# 40106PWM.net
KiCad netlist of a schematic drawn in EAGLE
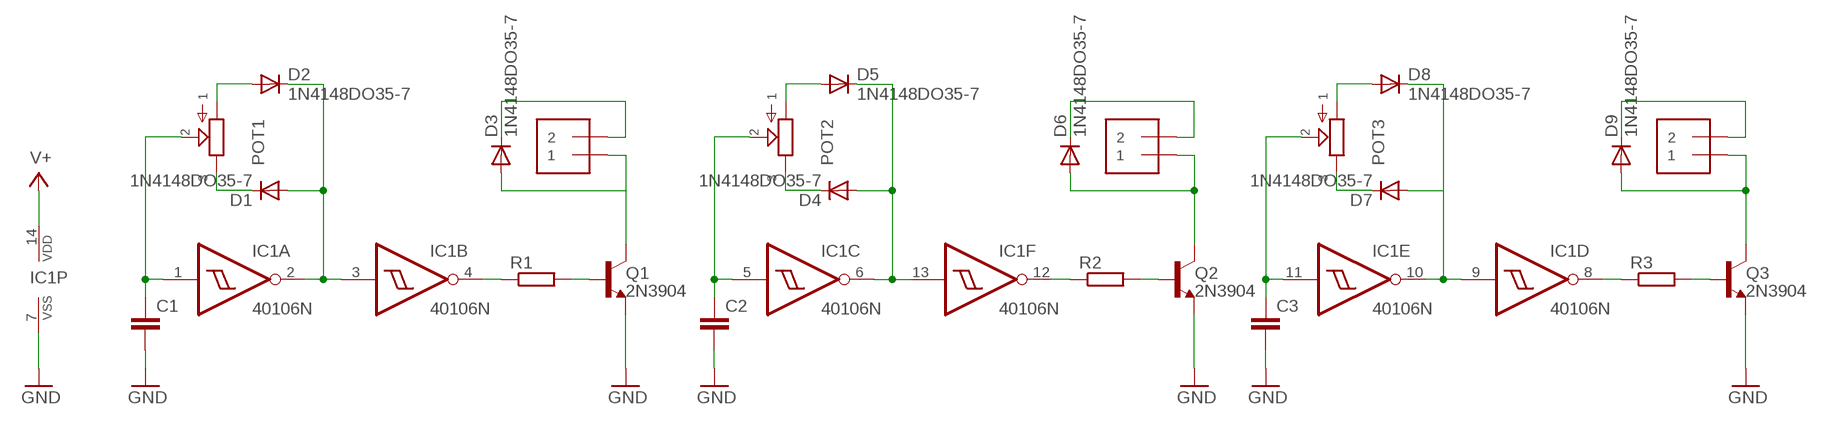
[diagram p0: schematic, sheet 1]

(export (version "E")
  (design (tool "Eeschema 10.0.6"))
  (components
    (comp (ref "C1")
      (value "C-EU050-025X075")
      (footprint "eagle-import:C050-025X075")
      (libsource (lib "eagle-import") (part "C-EU050-025X075"))
    )
    (comp (ref "C2")
      (value "C-EU050-025X075")
      (footprint "eagle-import:C050-025X075")
      (libsource (lib "eagle-import") (part "C-EU050-025X075"))
    )
    (comp (ref "C3")
      (value "C-EU050-025X075")
      (footprint "eagle-import:C050-025X075")
      (libsource (lib "eagle-import") (part "C-EU050-025X075"))
    )
    (comp (ref "D1")
      (value "1N4148DO35-7")
      (footprint "eagle-import:DO35-7")
      (libsource (lib "eagle-import") (part "1N4148DO35-7"))
    )
    (comp (ref "D2")
      (value "1N4148DO35-7")
      (footprint "eagle-import:DO35-7")
      (libsource (lib "eagle-import") (part "1N4148DO35-7"))
    )
    (comp (ref "D3")
      (value "1N4148DO35-7")
      (footprint "eagle-import:DO35-7")
      (libsource (lib "eagle-import") (part "1N4148DO35-7"))
    )
    (comp (ref "D4")
      (value "1N4148DO35-7")
      (footprint "eagle-import:DO35-7")
      (libsource (lib "eagle-import") (part "1N4148DO35-7"))
    )
    (comp (ref "D5")
      (value "1N4148DO35-7")
      (footprint "eagle-import:DO35-7")
      (libsource (lib "eagle-import") (part "1N4148DO35-7"))
    )
    (comp (ref "D6")
      (value "1N4148DO35-7")
      (footprint "eagle-import:DO35-7")
      (libsource (lib "eagle-import") (part "1N4148DO35-7"))
    )
    (comp (ref "D7")
      (value "1N4148DO35-7")
      (footprint "eagle-import:DO35-7")
      (libsource (lib "eagle-import") (part "1N4148DO35-7"))
    )
    (comp (ref "D8")
      (value "1N4148DO35-7")
      (footprint "eagle-import:DO35-7")
      (libsource (lib "eagle-import") (part "1N4148DO35-7"))
    )
    (comp (ref "D9")
      (value "1N4148DO35-7")
      (footprint "eagle-import:DO35-7")
      (libsource (lib "eagle-import") (part "1N4148DO35-7"))
    )
    (comp (ref "IC1")
      (value "40106N")
      (footprint "eagle-import:DIL14")
      (libsource (lib "eagle-import") (part "40106N"))
    )
    (comp (ref "J1")
      (value "1X2-3.5MM")
      (footprint "eagle-import:1X2-3.5MM")
      (libsource (lib "eagle-import") (part "1X2-3.5MM"))
    )
    (comp (ref "J2")
      (value "1X2-3.5MM")
      (footprint "eagle-import:1X2-3.5MM")
      (libsource (lib "eagle-import") (part "1X2-3.5MM"))
    )
    (comp (ref "J3")
      (value "1X2-3.5MM")
      (footprint "eagle-import:1X2-3.5MM")
      (libsource (lib "eagle-import") (part "1X2-3.5MM"))
    )
    (comp (ref "POT1")
      (value "POT-EU16MM")
      (footprint "eagle-import:16MM")
      (libsource (lib "eagle-import") (part "POT-EU16MM"))
    )
    (comp (ref "POT2")
      (value "POT-EU16MM")
      (footprint "eagle-import:16MM")
      (libsource (lib "eagle-import") (part "POT-EU16MM"))
    )
    (comp (ref "POT3")
      (value "POT-EU16MM")
      (footprint "eagle-import:16MM")
      (libsource (lib "eagle-import") (part "POT-EU16MM"))
    )
    (comp (ref "Q1")
      (value "2N3904")
      (footprint "eagle-import:TO92-")
      (libsource (lib "eagle-import") (part "2N3904"))
    )
    (comp (ref "Q2")
      (value "2N3904")
      (footprint "eagle-import:TO92-")
      (libsource (lib "eagle-import") (part "2N3904"))
    )
    (comp (ref "Q3")
      (value "2N3904")
      (footprint "eagle-import:TO92-")
      (libsource (lib "eagle-import") (part "2N3904"))
    )
    (comp (ref "R1")
      (value "R-EU_0207/10")
      (footprint "eagle-import:0207_10")
      (libsource (lib "eagle-import") (part "R-EU_0207/10"))
    )
    (comp (ref "R2")
      (value "R-EU_0207/10")
      (footprint "eagle-import:0207_10")
      (libsource (lib "eagle-import") (part "R-EU_0207/10"))
    )
    (comp (ref "R3")
      (value "R-EU_0207/10")
      (footprint "eagle-import:0207_10")
      (libsource (lib "eagle-import") (part "R-EU_0207/10"))
    )
  )
  (nets
    (net (code "1") (name "GND") (class "Default")
      (node (ref "C1") (pin "2") (pinfunction "2_2") (pintype "passive"))
      (node (ref "C2") (pin "2") (pinfunction "2_2") (pintype "passive"))
      (node (ref "C3") (pin "2") (pinfunction "2_2") (pintype "passive"))
      (node (ref "IC1") (pin "7") (pinfunction "VSS_7") (pintype "power_in"))
      (node (ref "Q1") (pin "3") (pinfunction "E_3") (pintype "passive"))
      (node (ref "Q2") (pin "3") (pinfunction "E_3") (pintype "passive"))
      (node (ref "Q3") (pin "3") (pinfunction "E_3") (pintype "passive"))
    )
    (net (code "2") (name "Net-(D1-PadC)") (class "Default")
      (node (ref "D1") (pin "C") (pinfunction "C_C") (pintype "passive"))
      (node (ref "POT1") (pin "3") (pinfunction "3_3") (pintype "passive"))
    )
    (net (code "3") (name "Net-(D2-PadA)") (class "Default")
      (node (ref "D2") (pin "A") (pinfunction "A_A") (pintype "passive"))
      (node (ref "POT1") (pin "1") (pinfunction "1_1") (pintype "passive"))
    )
    (net (code "4") (name "Net-(D3-PadC)") (class "Default")
      (node (ref "D3") (pin "C") (pinfunction "C_C") (pintype "passive"))
      (node (ref "J1") (pin "2") (pinfunction "2_2") (pintype "passive"))
    )
    (net (code "5") (name "Net-(D4-PadC)") (class "Default")
      (node (ref "D4") (pin "C") (pinfunction "C_C") (pintype "passive"))
      (node (ref "POT2") (pin "3") (pinfunction "3_3") (pintype "passive"))
    )
    (net (code "6") (name "Net-(D5-PadA)") (class "Default")
      (node (ref "D5") (pin "A") (pinfunction "A_A") (pintype "passive"))
      (node (ref "POT2") (pin "1") (pinfunction "1_1") (pintype "passive"))
    )
    (net (code "7") (name "Net-(D6-PadC)") (class "Default")
      (node (ref "D6") (pin "C") (pinfunction "C_C") (pintype "passive"))
      (node (ref "J2") (pin "2") (pinfunction "2_2") (pintype "passive"))
    )
    (net (code "8") (name "Net-(D7-PadC)") (class "Default")
      (node (ref "D7") (pin "C") (pinfunction "C_C") (pintype "passive"))
      (node (ref "POT3") (pin "3") (pinfunction "3_3") (pintype "passive"))
    )
    (net (code "9") (name "Net-(D8-PadA)") (class "Default")
      (node (ref "D8") (pin "A") (pinfunction "A_A") (pintype "passive"))
      (node (ref "POT3") (pin "1") (pinfunction "1_1") (pintype "passive"))
    )
    (net (code "10") (name "Net-(D9-PadC)") (class "Default")
      (node (ref "D9") (pin "C") (pinfunction "C_C") (pintype "passive"))
      (node (ref "J3") (pin "2") (pinfunction "2_2") (pintype "passive"))
    )
    (net (code "11") (name "Net-(IC1A-I)") (class "Default")
      (node (ref "C1") (pin "1") (pinfunction "1_1") (pintype "passive"))
      (node (ref "IC1") (pin "1") (pinfunction "I_1") (pintype "input"))
      (node (ref "POT1") (pin "2") (pinfunction "2_2") (pintype "passive"))
    )
    (net (code "12") (name "Net-(IC1A-O)") (class "Default")
      (node (ref "D1") (pin "A") (pinfunction "A_A") (pintype "passive"))
      (node (ref "D2") (pin "C") (pinfunction "C_C") (pintype "passive"))
      (node (ref "IC1") (pin "2") (pinfunction "O_2") (pintype "output"))
      (node (ref "IC1") (pin "3") (pinfunction "I_3") (pintype "input"))
    )
    (net (code "13") (name "Net-(IC1B-O)") (class "Default")
      (node (ref "IC1") (pin "4") (pinfunction "O_4") (pintype "output"))
      (node (ref "R1") (pin "1") (pinfunction "1_1") (pintype "passive"))
    )
    (net (code "14") (name "Net-(IC1C-I)") (class "Default")
      (node (ref "C2") (pin "1") (pinfunction "1_1") (pintype "passive"))
      (node (ref "IC1") (pin "5") (pinfunction "I_5") (pintype "input"))
      (node (ref "POT2") (pin "2") (pinfunction "2_2") (pintype "passive"))
    )
    (net (code "15") (name "Net-(IC1C-O)") (class "Default")
      (node (ref "D4") (pin "A") (pinfunction "A_A") (pintype "passive"))
      (node (ref "D5") (pin "C") (pinfunction "C_C") (pintype "passive"))
      (node (ref "IC1") (pin "13") (pinfunction "I_13") (pintype "input"))
      (node (ref "IC1") (pin "6") (pinfunction "O_6") (pintype "output"))
    )
    (net (code "16") (name "Net-(IC1D-I)") (class "Default")
      (node (ref "D7") (pin "A") (pinfunction "A_A") (pintype "passive"))
      (node (ref "D8") (pin "C") (pinfunction "C_C") (pintype "passive"))
      (node (ref "IC1") (pin "10") (pinfunction "O_10") (pintype "output"))
      (node (ref "IC1") (pin "9") (pinfunction "I_9") (pintype "input"))
    )
    (net (code "17") (name "Net-(IC1D-O)") (class "Default")
      (node (ref "IC1") (pin "8") (pinfunction "O_8") (pintype "output"))
      (node (ref "R3") (pin "1") (pinfunction "1_1") (pintype "passive"))
    )
    (net (code "18") (name "Net-(IC1E-I)") (class "Default")
      (node (ref "C3") (pin "1") (pinfunction "1_1") (pintype "passive"))
      (node (ref "IC1") (pin "11") (pinfunction "I_11") (pintype "input"))
      (node (ref "POT3") (pin "2") (pinfunction "2_2") (pintype "passive"))
    )
    (net (code "19") (name "Net-(IC1F-O)") (class "Default")
      (node (ref "IC1") (pin "12") (pinfunction "O_12") (pintype "output"))
      (node (ref "R2") (pin "1") (pinfunction "1_1") (pintype "passive"))
    )
    (net (code "20") (name "Net-(Q1-B)") (class "Default")
      (node (ref "Q1") (pin "2") (pinfunction "B_2") (pintype "passive"))
      (node (ref "R1") (pin "2") (pinfunction "2_2") (pintype "passive"))
    )
    (net (code "21") (name "Net-(Q1-C)") (class "Default")
      (node (ref "D3") (pin "A") (pinfunction "A_A") (pintype "passive"))
      (node (ref "J1") (pin "1") (pinfunction "1_1") (pintype "passive"))
      (node (ref "Q1") (pin "1") (pinfunction "C_1") (pintype "passive"))
    )
    (net (code "22") (name "Net-(Q2-B)") (class "Default")
      (node (ref "Q2") (pin "2") (pinfunction "B_2") (pintype "passive"))
      (node (ref "R2") (pin "2") (pinfunction "2_2") (pintype "passive"))
    )
    (net (code "23") (name "Net-(Q2-C)") (class "Default")
      (node (ref "D6") (pin "A") (pinfunction "A_A") (pintype "passive"))
      (node (ref "J2") (pin "1") (pinfunction "1_1") (pintype "passive"))
      (node (ref "Q2") (pin "1") (pinfunction "C_1") (pintype "passive"))
    )
    (net (code "24") (name "Net-(Q3-B)") (class "Default")
      (node (ref "Q3") (pin "2") (pinfunction "B_2") (pintype "passive"))
      (node (ref "R3") (pin "2") (pinfunction "2_2") (pintype "passive"))
    )
    (net (code "25") (name "Net-(Q3-C)") (class "Default")
      (node (ref "D9") (pin "A") (pinfunction "A_A") (pintype "passive"))
      (node (ref "J3") (pin "1") (pinfunction "1_1") (pintype "passive"))
      (node (ref "Q3") (pin "1") (pinfunction "C_1") (pintype "passive"))
    )
    (net (code "26") (name "V+") (class "Default")
      (node (ref "IC1") (pin "14") (pinfunction "VDD_14") (pintype "power_in"))
    )
  )
)
